# SCH_Navigation_Remote.net
KiCad netlist of a schematic drawn in EasyEDA
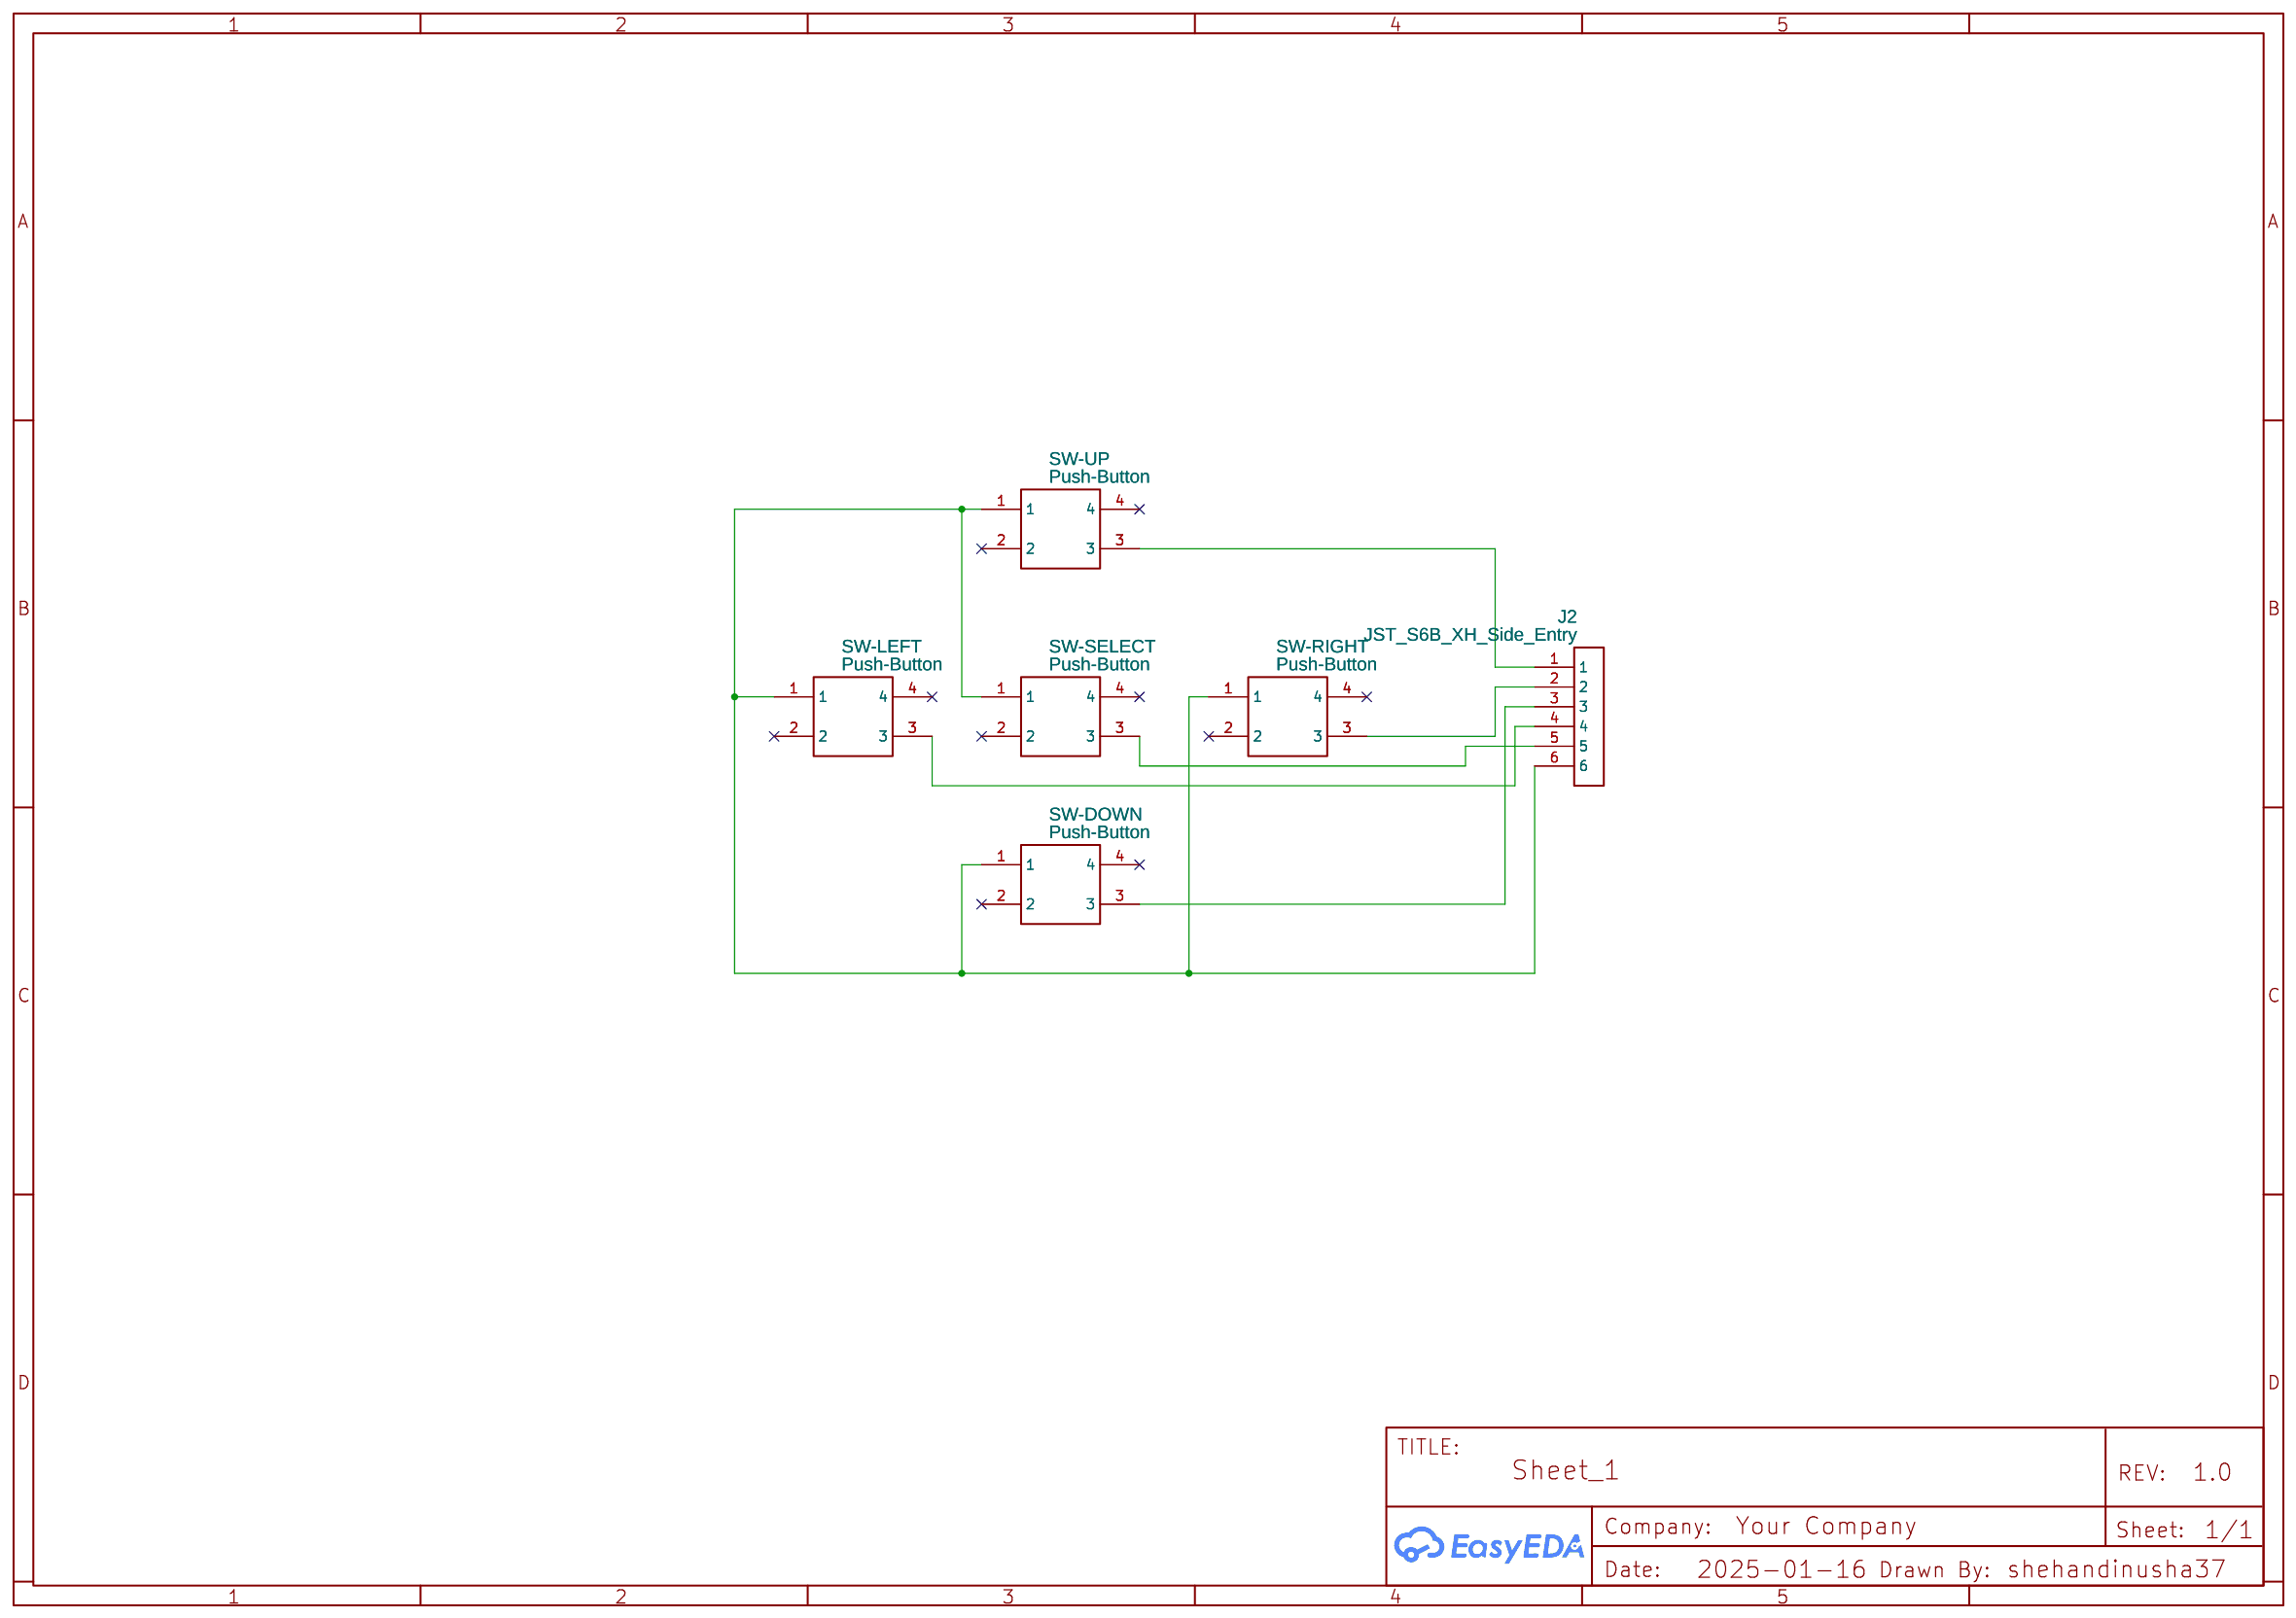
[diagram p0: schematic sheet]

(export (version "E")
  (design (tool "Eeschema 10.0.6"))
  (components
    (comp (ref "J2") (value "JST_S6B_XH_Side_Entry") (libsource (lib "") (part "JST_S6B_XH_Side_Entry")))
    (comp (ref "SW-DOWN") (value "Push-Button") (libsource (lib "") (part "PB 200 x 500 - 2_1")))
    (comp (ref "SW-LEFT") (value "Push-Button") (libsource (lib "") (part "PB 200 x 500 - 2_4")))
    (comp (ref "SW-RIGHT") (value "Push-Button") (libsource (lib "") (part "PB 200 x 500 - 2_2")))
    (comp (ref "SW-SELECT") (value "Push-Button") (libsource (lib "") (part "PB 200 x 500 - 2")))
    (comp (ref "SW-UP") (value "Push-Button") (libsource (lib "") (part "PB 200 x 500 - 2_3")))
  )
  (nets
    (net (code "1") (name "Net-(J2-Pad1)") (class "Default")
      (node (ref "J2") (pin "1") (pinfunction "1_1") (pintype "unspecified"))
      (node (ref "SW-UP") (pin "3") (pinfunction "3_3") (pintype "unspecified"))
    )
    (net (code "2") (name "Net-(J2-Pad2)") (class "Default")
      (node (ref "J2") (pin "2") (pinfunction "2_2") (pintype "unspecified"))
      (node (ref "SW-RIGHT") (pin "3") (pinfunction "3_3") (pintype "unspecified"))
    )
    (net (code "3") (name "Net-(J2-Pad3)") (class "Default")
      (node (ref "J2") (pin "3") (pinfunction "3_3") (pintype "unspecified"))
      (node (ref "SW-DOWN") (pin "3") (pinfunction "3_3") (pintype "unspecified"))
    )
    (net (code "4") (name "Net-(J2-Pad4)") (class "Default")
      (node (ref "J2") (pin "4") (pinfunction "4_4") (pintype "unspecified"))
      (node (ref "SW-LEFT") (pin "3") (pinfunction "3_3") (pintype "unspecified"))
    )
    (net (code "5") (name "Net-(J2-Pad5)") (class "Default")
      (node (ref "J2") (pin "5") (pinfunction "5_5") (pintype "unspecified"))
      (node (ref "SW-SELECT") (pin "3") (pinfunction "3_3") (pintype "unspecified"))
    )
    (net (code "6") (name "Net-(J2-Pad6)") (class "Default")
      (node (ref "J2") (pin "6") (pinfunction "6_6") (pintype "unspecified"))
      (node (ref "SW-DOWN") (pin "1") (pinfunction "1_1") (pintype "unspecified"))
      (node (ref "SW-LEFT") (pin "1") (pinfunction "1_1") (pintype "unspecified"))
      (node (ref "SW-RIGHT") (pin "1") (pinfunction "1_1") (pintype "unspecified"))
      (node (ref "SW-SELECT") (pin "1") (pinfunction "1_1") (pintype "unspecified"))
      (node (ref "SW-UP") (pin "1") (pinfunction "1_1") (pintype "unspecified"))
    )
    (net (code "7") (name "unconnected-(SW-DOWN-Pad2)") (class "Default")
      (node (ref "SW-DOWN") (pin "2") (pinfunction "2_2") (pintype "unspecified+no_connect"))
    )
    (net (code "8") (name "unconnected-(SW-DOWN-Pad4)") (class "Default")
      (node (ref "SW-DOWN") (pin "4") (pinfunction "4_4") (pintype "unspecified+no_connect"))
    )
    (net (code "9") (name "unconnected-(SW-LEFT-Pad2)") (class "Default")
      (node (ref "SW-LEFT") (pin "2") (pinfunction "2_2") (pintype "unspecified+no_connect"))
    )
    (net (code "10") (name "unconnected-(SW-LEFT-Pad4)") (class "Default")
      (node (ref "SW-LEFT") (pin "4") (pinfunction "4_4") (pintype "unspecified+no_connect"))
    )
    (net (code "11") (name "unconnected-(SW-RIGHT-Pad2)") (class "Default")
      (node (ref "SW-RIGHT") (pin "2") (pinfunction "2_2") (pintype "unspecified+no_connect"))
    )
    (net (code "12") (name "unconnected-(SW-RIGHT-Pad4)") (class "Default")
      (node (ref "SW-RIGHT") (pin "4") (pinfunction "4_4") (pintype "unspecified+no_connect"))
    )
    (net (code "13") (name "unconnected-(SW-SELECT-Pad2)") (class "Default")
      (node (ref "SW-SELECT") (pin "2") (pinfunction "2_2") (pintype "unspecified+no_connect"))
    )
    (net (code "14") (name "unconnected-(SW-SELECT-Pad4)") (class "Default")
      (node (ref "SW-SELECT") (pin "4") (pinfunction "4_4") (pintype "unspecified+no_connect"))
    )
    (net (code "15") (name "unconnected-(SW-UP-Pad2)") (class "Default")
      (node (ref "SW-UP") (pin "2") (pinfunction "2_2") (pintype "unspecified+no_connect"))
    )
    (net (code "16") (name "unconnected-(SW-UP-Pad4)") (class "Default")
      (node (ref "SW-UP") (pin "4") (pinfunction "4_4") (pintype "unspecified+no_connect"))
    )
  )
)
